# Copy_of_Power.net
KiCad netlist of a schematic drawn in Altium Designer
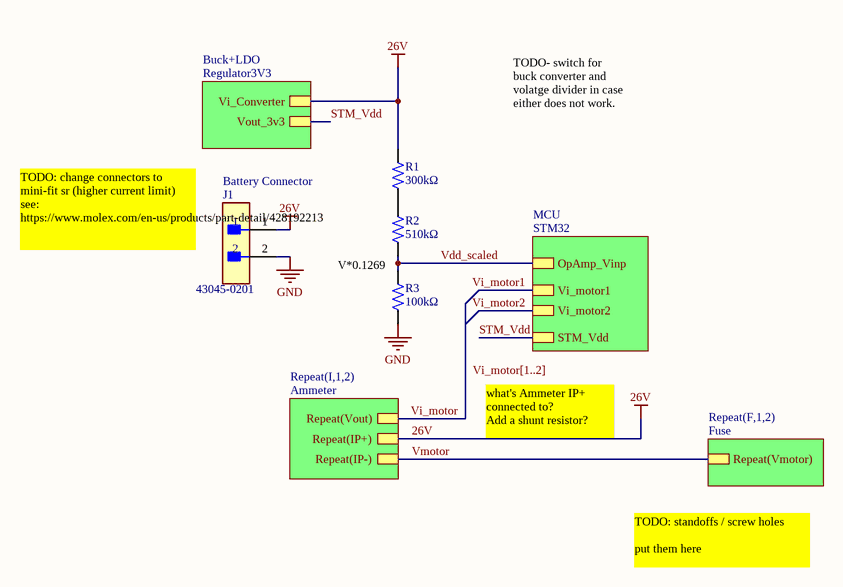
[diagram p0: Copy of Power.SchDoc]

(export (version "E")
  (design (tool "Eeschema 10.0.6"))
  (components
    (comp (ref "J1")
      (value "43045-0201")
      (footprint "FP-43045-0201-MFG")
      (description "CONN HEADER R/A 2POS")
      (libsource (lib "Altium Content Vault") (part "3bc925449376181038e59eaffc5286c"))
    )
    (comp (ref "R1")
      (value "0603WAF3003T5E")
      (footprint "RES-0603")
      (description "Resistor, 300kΩ, ±1%, 100mW, 75V, ±100ppm/℃, -55℃~+155℃, SMD 0603")
      (fields
        (field (name "MANUFACTURER") "Uniroyal")
        (field (name "JLCPCB PART NUMBER") "C23024")
        (field (name "RESISTANCE") "300kΩ")
      )
      (libsource (lib "jlcpcb_2024_10_resistors_basic") (part "0603WAF3003T5E"))
    )
    (comp (ref "R2")
      (value "0603WAF5103T5E")
      (footprint "RES-0603")
      (description "Resistor, 510kΩ, ±1%, 100mW, 75V, ±100ppm/℃, -55℃~+155℃, SMD 0603")
      (fields
        (field (name "MANUFACTURER") "Uniroyal")
        (field (name "JLCPCB PART NUMBER") "C23192")
        (field (name "RESISTANCE") "510kΩ")
      )
      (libsource (lib "jlcpcb_2024_10_resistors_basic") (part "0603WAF5103T5E"))
    )
    (comp (ref "R3")
      (value "0402WGF1003TCE")
      (footprint "RES-0402")
      (description "Resistor, 100kΩ, ±1%, 62.5mW, 50V, ±100ppm/℃, -55℃~+155℃, SMD 0402")
      (fields
        (field (name "MANUFACTURER") "Uniroyal")
        (field (name "JLCPCB PART NUMBER") "C25741")
        (field (name "RESISTANCE") "100kΩ")
      )
      (libsource (lib "jlcpcb_2024_10_resistors_basic") (part "0402WGF1003TCE"))
    )
  )
  (nets
    (net (code "3") (name "/Vdd_scaled") (class "Default")
      (node (ref "R2") (pin "1") (pinfunction "1_1") (pintype "passive"))
      (node (ref "R3") (pin "2") (pinfunction "2_2") (pintype "passive"))
    )
    (net (code "9") (name "26V") (class "Default")
      (node (ref "J1") (pin "1") (pinfunction "1_1") (pintype "passive"))
      (node (ref "R1") (pin "2") (pinfunction "2_2") (pintype "passive"))
    )
    (net (code "10") (name "GND") (class "Default")
      (node (ref "J1") (pin "2") (pinfunction "2_2") (pintype "passive"))
      (node (ref "R3") (pin "1") (pinfunction "1_1") (pintype "passive"))
    )
    (net (code "11") (name "Net-(R1-Pad1)") (class "Default")
      (node (ref "R1") (pin "1") (pinfunction "1_1") (pintype "passive"))
      (node (ref "R2") (pin "2") (pinfunction "2_2") (pintype "passive"))
    )
  )
)
